# crystalLEDControl.net
KiCad netlist of a schematic drawn in EAGLE
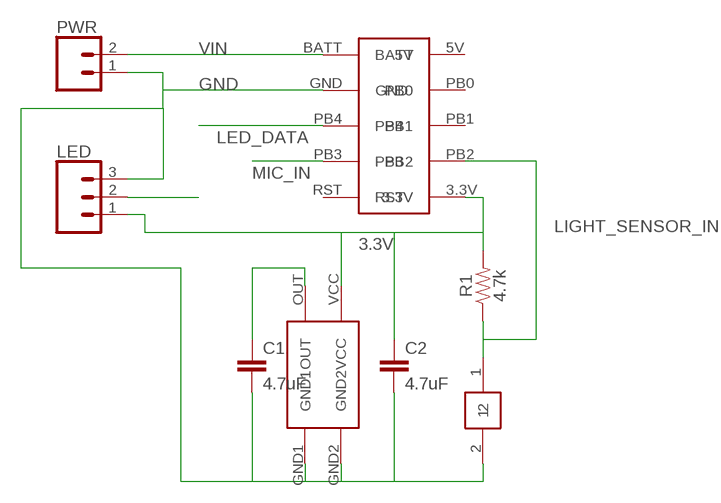
[diagram p0: schematic, sheet 1]

(export (version "E")
  (design (tool "Eeschema 10.0.6"))
  (components
    (comp (ref "A1")
      (value "SPW2430")
      (footprint "eagle-import:SPW2430")
      (libsource (lib "eagle-import") (part "SPW2430"))
    )
    (comp (ref "C1")
      (value "4.7uF")
      (footprint "eagle-import:0603")
      (libsource (lib "eagle-import") (part "4.7UF0603"))
    )
    (comp (ref "C2")
      (value "4.7uF")
      (footprint "eagle-import:0603")
      (libsource (lib "eagle-import") (part "4.7UF0603"))
    )
    (comp (ref "LED")
      (value "CONN_03")
      (footprint "eagle-import:1X03")
      (libsource (lib "eagle-import") (part "CONN_03"))
    )
    (comp (ref "MCU1")
      (value "ARDUINO_TRINKET")
      (footprint "eagle-import:ARDUINO_TRINKET")
      (libsource (lib "eagle-import") (part "ARDUINO_TRINKET"))
    )
    (comp (ref "PC1")
      (value "PDV-P8101")
      (footprint "eagle-import:PHOTOCELL_CERAMIC")
      (libsource (lib "eagle-import") (part "PDV-P8101"))
    )
    (comp (ref "PWR")
      (value "CONN_02")
      (footprint "eagle-import:1X02")
      (libsource (lib "eagle-import") (part "CONN_02"))
    )
    (comp (ref "R1")
      (value "4.7k")
      (footprint "eagle-import:0603")
      (libsource (lib "eagle-import") (part "4.7KOHM-0603-1/10W-1%"))
    )
  )
  (nets
    (net (code "1") (name "/3.3V") (class "Default")
      (node (ref "A1") (pin "VCC") (pinfunction "VCC_VCC") (pintype "bidirectional"))
      (node (ref "C2") (pin "1") (pinfunction "1_1") (pintype "passive"))
      (node (ref "LED") (pin "1") (pinfunction "1_1") (pintype "passive"))
      (node (ref "MCU1") (pin "3.3V") (pinfunction "3.3V_3.3V") (pintype "bidirectional"))
      (node (ref "R1") (pin "2") (pinfunction "2_2") (pintype "passive"))
    )
    (net (code "2") (name "/GND") (class "Default")
      (node (ref "A1") (pin "GND1") (pinfunction "GND1_GND1") (pintype "bidirectional"))
      (node (ref "A1") (pin "GND2") (pinfunction "GND2_GND2") (pintype "bidirectional"))
      (node (ref "C1") (pin "2") (pinfunction "2_2") (pintype "passive"))
      (node (ref "C2") (pin "2") (pinfunction "2_2") (pintype "passive"))
      (node (ref "LED") (pin "3") (pinfunction "3_3") (pintype "passive"))
      (node (ref "MCU1") (pin "GND") (pinfunction "GND_GND") (pintype "bidirectional"))
      (node (ref "PC1") (pin "2") (pinfunction "2_2") (pintype "bidirectional"))
      (node (ref "PWR") (pin "1") (pinfunction "1_1") (pintype "passive"))
    )
    (net (code "3") (name "/LED_DATA") (class "Default")
      (node (ref "LED") (pin "2") (pinfunction "2_2") (pintype "passive"))
      (node (ref "MCU1") (pin "PB4") (pinfunction "PB4_PB4") (pintype "bidirectional"))
    )
    (net (code "4") (name "/LIGHT_SENSOR_IN") (class "Default")
      (node (ref "MCU1") (pin "PB2") (pinfunction "PB2_PB2") (pintype "bidirectional"))
      (node (ref "PC1") (pin "1") (pinfunction "1_1") (pintype "bidirectional"))
      (node (ref "R1") (pin "1") (pinfunction "1_1") (pintype "passive"))
    )
    (net (code "5") (name "/MIC_IN") (class "Default")
      (node (ref "A1") (pin "OUT") (pinfunction "OUT_OUT") (pintype "bidirectional"))
      (node (ref "C1") (pin "1") (pinfunction "1_1") (pintype "passive"))
      (node (ref "MCU1") (pin "PB3") (pinfunction "PB3_PB3") (pintype "bidirectional"))
    )
    (net (code "6") (name "/VIN") (class "Default")
      (node (ref "MCU1") (pin "BATT") (pinfunction "BATT_BATT") (pintype "bidirectional"))
      (node (ref "PWR") (pin "2") (pinfunction "2_2") (pintype "passive"))
    )
    (net (code "7") (name "unconnected-(MCU1-Pad5V)") (class "Default")
      (node (ref "MCU1") (pin "5V") (pinfunction "5V_5V") (pintype "bidirectional"))
    )
    (net (code "8") (name "unconnected-(MCU1-PadPB0)") (class "Default")
      (node (ref "MCU1") (pin "PB0") (pinfunction "PB0_PB0") (pintype "bidirectional"))
    )
    (net (code "9") (name "unconnected-(MCU1-PadPB1)") (class "Default")
      (node (ref "MCU1") (pin "PB1") (pinfunction "PB1_PB1") (pintype "bidirectional"))
    )
    (net (code "10") (name "unconnected-(MCU1-PadRST)") (class "Default")
      (node (ref "MCU1") (pin "RST") (pinfunction "RST_RST") (pintype "bidirectional"))
    )
  )
)
